# SW6208_A_A_B_C_LED__188.net
KiCad netlist of a schematic drawn in Altium Designer
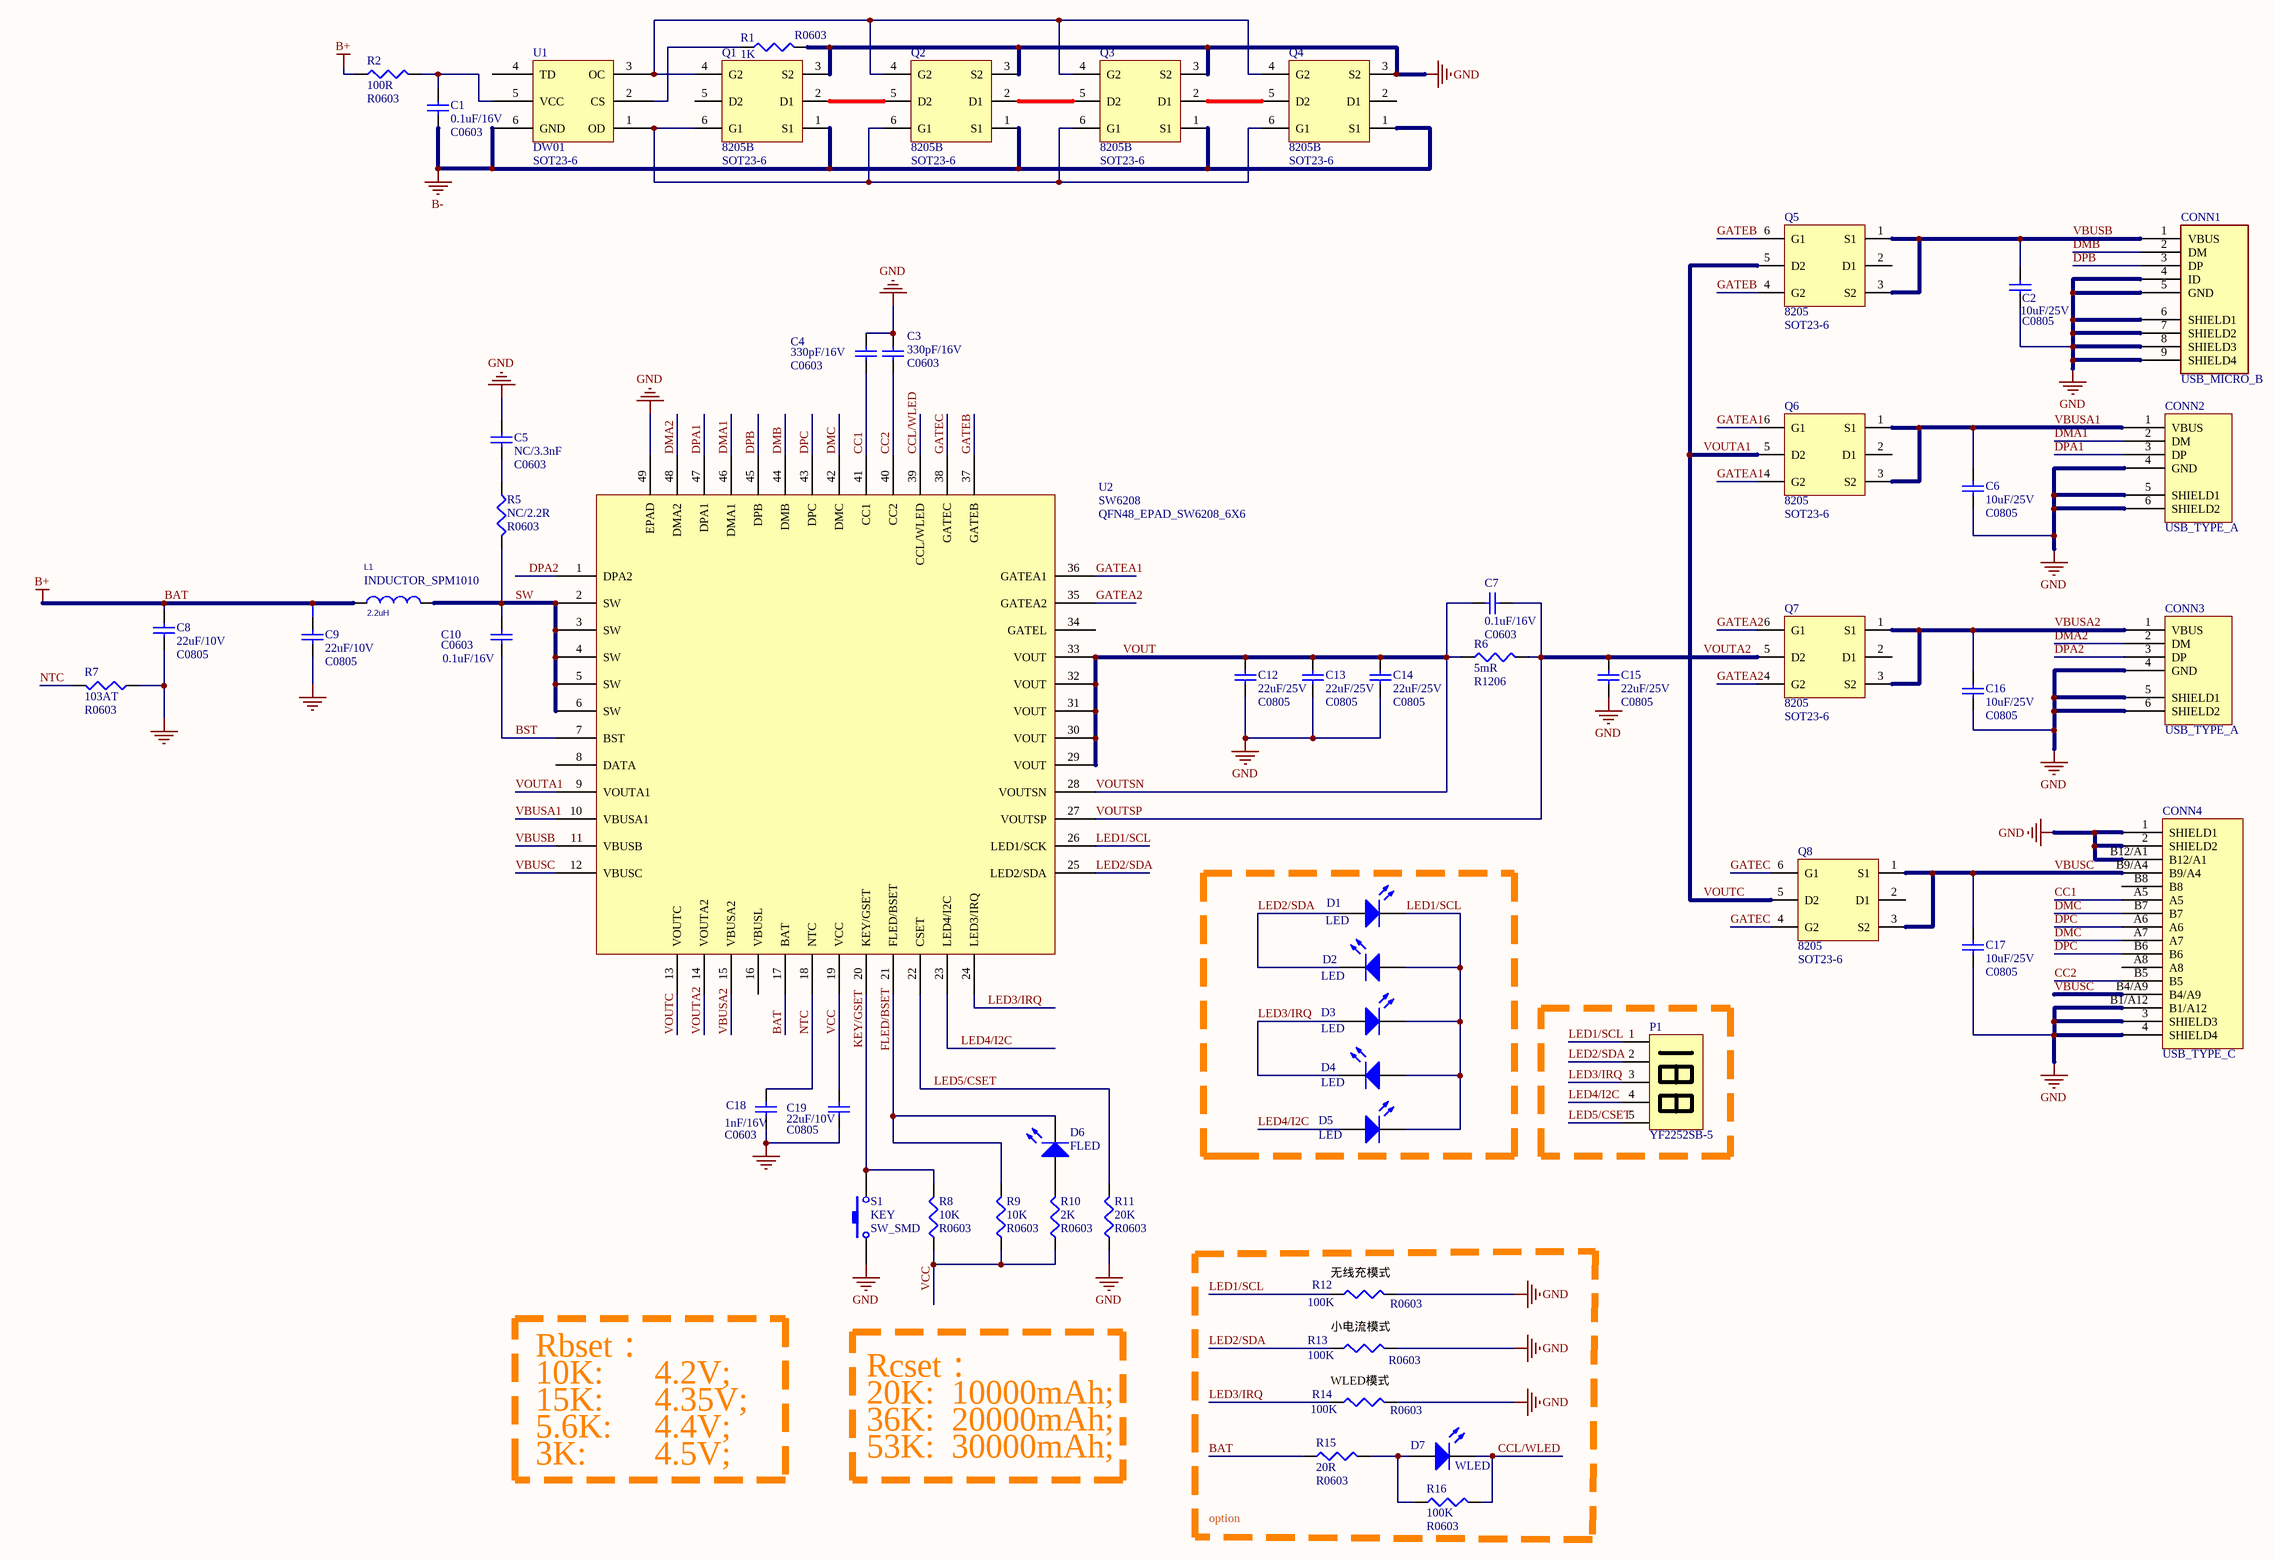
[diagram p0: SW6208+A+A+B+C+LED_普通188数码管.SchDoc]

(export (version "E")
  (design (tool "Eeschema 10.0.6"))
  (components
    (comp (ref "C1")
      (value "0.1uF/16V")
      (footprint "C0603")
      (description "Capacitor")
      (fields (field (name "PUBLISHER") "Altium Limited"))
      (libsource (lib "参考设计器件原理图更新") (part "CAP0603"))
    )
    (comp (ref "C2")
      (value "10uF/25V")
      (footprint "C0805")
      (description "Capacitor")
      (fields (field (name "PUBLISHER") "Altium Limited"))
      (libsource (lib "参考设计器件原理图更新") (part "CAP0805"))
    )
    (comp (ref "C3")
      (value "330pF/16V")
      (footprint "C0603")
      (description "Capacitor")
      (fields (field (name "PUBLISHER") "Altium Limited"))
      (libsource (lib "参考设计器件原理图更新") (part "CAP0603"))
    )
    (comp (ref "C4")
      (value "330pF/16V")
      (footprint "C0603")
      (description "Capacitor")
      (fields (field (name "PUBLISHER") "Altium Limited"))
      (libsource (lib "参考设计器件原理图更新") (part "CAP0603"))
    )
    (comp (ref "C5")
      (value "NC/3.3nF")
      (footprint "C0603")
      (description "Capacitor")
      (fields (field (name "PUBLISHER") "Altium Limited"))
      (libsource (lib "参考设计器件原理图更新") (part "CAP0603"))
    )
    (comp (ref "C6")
      (value "10uF/25V")
      (footprint "C0805")
      (description "Capacitor")
      (fields (field (name "PUBLISHER") "Altium Limited"))
      (libsource (lib "参考设计器件原理图更新") (part "CAP0805"))
    )
    (comp (ref "C7")
      (value "0.1uF/16V")
      (footprint "C0603")
      (description "Capacitor")
      (fields (field (name "PUBLISHER") "Altium Limited"))
      (libsource (lib "参考设计器件原理图更新") (part "CAP0603"))
    )
    (comp (ref "C8")
      (value "22uF/10V")
      (footprint "C0805")
      (description "Capacitor")
      (fields (field (name "PUBLISHER") "Altium Limited"))
      (libsource (lib "参考设计器件原理图更新") (part "CAP0805"))
    )
    (comp (ref "C9")
      (value "22uF/10V")
      (footprint "C0805")
      (description "Capacitor")
      (fields (field (name "PUBLISHER") "Altium Limited"))
      (libsource (lib "参考设计器件原理图更新") (part "CAP0805"))
    )
    (comp (ref "C10")
      (value "0.1uF/16V")
      (footprint "C0603")
      (description "Capacitor")
      (fields (field (name "PUBLISHER") "Altium Limited"))
      (libsource (lib "参考设计器件原理图更新") (part "CAP0603"))
    )
    (comp (ref "C12")
      (value "22uF/25V")
      (footprint "C0805")
      (description "Capacitor")
      (fields (field (name "PUBLISHER") "Altium Limited"))
      (libsource (lib "参考设计器件原理图更新") (part "CAP0805"))
    )
    (comp (ref "C13")
      (value "22uF/25V")
      (footprint "C0805")
      (description "Capacitor")
      (fields (field (name "PUBLISHER") "Altium Limited"))
      (libsource (lib "参考设计器件原理图更新") (part "CAP0805"))
    )
    (comp (ref "C14")
      (value "22uF/25V")
      (footprint "C0805")
      (description "Capacitor")
      (fields (field (name "PUBLISHER") "Altium Limited"))
      (libsource (lib "参考设计器件原理图更新") (part "CAP0805"))
    )
    (comp (ref "C15")
      (value "22uF/25V")
      (footprint "C0805")
      (description "Capacitor")
      (fields (field (name "PUBLISHER") "Altium Limited"))
      (libsource (lib "参考设计器件原理图更新") (part "CAP0805"))
    )
    (comp (ref "C16")
      (value "10uF/25V")
      (footprint "C0805")
      (description "Capacitor")
      (fields (field (name "PUBLISHER") "Altium Limited"))
      (libsource (lib "参考设计器件原理图更新") (part "CAP0805"))
    )
    (comp (ref "C17")
      (value "10uF/25V")
      (footprint "C0805")
      (description "Capacitor")
      (fields (field (name "PUBLISHER") "Altium Limited"))
      (libsource (lib "参考设计器件原理图更新") (part "CAP0805"))
    )
    (comp (ref "C18")
      (value "1nF/16V")
      (footprint "C0603")
      (description "Capacitor")
      (fields (field (name "PUBLISHER") "Altium Limited"))
      (libsource (lib "参考设计器件原理图更新") (part "CAP0603"))
    )
    (comp (ref "C19")
      (value "22uF/10V")
      (footprint "C0805")
      (description "Capacitor")
      (fields (field (name "PUBLISHER") "Altium Limited"))
      (libsource (lib "参考设计器件原理图更新") (part "CAP0805"))
    )
    (comp (ref "CONN1")
      (value "USB_MICRO_B")
      (footprint "USB_MICRO_B")
      (libsource (lib "参考设计器件原理图更新") (part "USB_MICRO_B"))
    )
    (comp (ref "CONN2")
      (value "USB_TYPE_A")
      (footprint "USB_TYPE_A")
      (libsource (lib "参考设计器件原理图更新") (part "USB_TYPE_A"))
    )
    (comp (ref "CONN3")
      (value "USB_TYPE_A")
      (footprint "USB_TYPE_A")
      (libsource (lib "参考设计器件原理图更新") (part "USB_TYPE_A"))
    )
    (comp (ref "CONN4")
      (value "USB_TYPE_C")
      (footprint "LOUISAD:USB_TYPE_C")
      (libsource (lib "参考设计器件原理图更新") (part "USB_TYPE_C"))
    )
    (comp (ref "D1")
      (value "LED")
      (footprint "LED0603")
      (fields (field (name "PUBLISHER") "Altium Limited"))
      (libsource (lib "参考设计器件原理图更新") (part "LED_0603"))
    )
    (comp (ref "D2")
      (value "LED")
      (footprint "LED0603")
      (fields (field (name "PUBLISHER") "Altium Limited"))
      (libsource (lib "参考设计器件原理图更新") (part "LED_0603"))
    )
    (comp (ref "D3")
      (value "LED")
      (footprint "LED0603")
      (fields (field (name "PUBLISHER") "Altium Limited"))
      (libsource (lib "参考设计器件原理图更新") (part "LED_0603"))
    )
    (comp (ref "D4")
      (value "LED")
      (footprint "LED0603")
      (fields (field (name "PUBLISHER") "Altium Limited"))
      (libsource (lib "参考设计器件原理图更新") (part "LED_0603"))
    )
    (comp (ref "D5")
      (value "LED")
      (footprint "LED0603")
      (fields (field (name "PUBLISHER") "Altium Limited"))
      (libsource (lib "参考设计器件原理图更新") (part "LED_0603"))
    )
    (comp (ref "D6")
      (value "FLED")
      (footprint "LED0603")
      (description "LED")
      (fields (field (name "PUBLISHER") "Altium Limited"))
      (libsource (lib "参考设计器件原理图更新") (part "LED_0603"))
    )
    (comp (ref "D7")
      (value "WLED")
      (footprint "LED_5MM")
      (fields (field (name "PUBLISHER") "Altium Limited"))
      (libsource (lib "参考设计器件原理图更新") (part "WLED"))
    )
    (comp (ref "L1")
      (value "2.2uH")
      (footprint "INDUCTOR_SPM1010")
      (description "INDUCTOR")
      (libsource (lib "参考设计器件原理图更新") (part "INDUCTOR_SPM1010"))
    )
    (comp (ref "P1")
      (value "YF2252SB-5")
      (footprint "LED_Display_5")
      (description "188_LED_Display")
      (libsource (lib "参考设计器件原理图更新") (part "LED_Display_5"))
    )
    (comp (ref "Q1")
      (value "8205B")
      (footprint "SOT23-6")
      (description "NMOS")
      (fields (field (name "FOOTPRINF") "SOT23-6"))
      (libsource (lib "参考设计器件原理图更新") (part "8205"))
    )
    (comp (ref "Q2")
      (value "8205B")
      (footprint "SOT23-6")
      (description "NMOS")
      (fields (field (name "FOOTPRINF") "SOT23-6"))
      (libsource (lib "参考设计器件原理图更新") (part "8205"))
    )
    (comp (ref "Q3")
      (value "8205B")
      (footprint "SOT23-6")
      (description "NMOS")
      (fields (field (name "FOOTPRINF") "SOT23-6"))
      (libsource (lib "参考设计器件原理图更新") (part "8205"))
    )
    (comp (ref "Q4")
      (value "8205B")
      (footprint "SOT23-6")
      (description "NMOS")
      (fields (field (name "FOOTPRINF") "SOT23-6"))
      (libsource (lib "参考设计器件原理图更新") (part "8205"))
    )
    (comp (ref "Q5")
      (value "8205")
      (footprint "SOT23-6")
      (description "NMOS")
      (fields (field (name "FOOTPRINF") "SOT23-6"))
      (libsource (lib "") (part "8205_1"))
    )
    (comp (ref "Q6")
      (value "8205")
      (footprint "SOT23-6")
      (description "NMOS")
      (fields (field (name "FOOTPRINF") "SOT23-6"))
      (libsource (lib "") (part "8205_1"))
    )
    (comp (ref "Q7")
      (value "8205")
      (footprint "SOT23-6")
      (description "NMOS")
      (fields (field (name "FOOTPRINF") "SOT23-6"))
      (libsource (lib "") (part "8205_1"))
    )
    (comp (ref "Q8")
      (value "8205")
      (footprint "SOT23-6")
      (description "NMOS")
      (fields (field (name "FOOTPRINF") "SOT23-6"))
      (libsource (lib "") (part "8205_1"))
    )
    (comp (ref "R1")
      (value "1K")
      (footprint "R0603")
      (description "Resistor")
      (fields (field (name "PUBLISHER") "Altium Limited"))
      (libsource (lib "参考设计器件原理图更新") (part "RES_0603"))
    )
    (comp (ref "R2")
      (value "100R")
      (footprint "R0603")
      (description "Resistor")
      (fields (field (name "PUBLISHER") "Altium Limited"))
      (libsource (lib "参考设计器件原理图更新") (part "RES_0603"))
    )
    (comp (ref "R5")
      (value "NC/2.2R")
      (footprint "R0603")
      (description "Resistor")
      (fields (field (name "PUBLISHER") "Altium Limited"))
      (libsource (lib "参考设计器件原理图更新") (part "RES_0603"))
    )
    (comp (ref "R6")
      (value "5mR")
      (footprint "R1206")
      (description "Resistor")
      (fields (field (name "PUBLISHER") "Altium Limited"))
      (libsource (lib "参考设计器件原理图更新") (part "RES_1206"))
    )
    (comp (ref "R7")
      (value "103AT")
      (footprint "R0603")
      (description "Resistor")
      (fields (field (name "PUBLISHER") "Altium Limited"))
      (libsource (lib "参考设计器件原理图更新") (part "RES_0603"))
    )
    (comp (ref "R8")
      (value "10K")
      (footprint "R0603")
      (description "Resistor")
      (fields (field (name "PUBLISHER") "Altium Limited"))
      (libsource (lib "参考设计器件原理图更新") (part "RES_0603"))
    )
    (comp (ref "R9")
      (value "10K")
      (footprint "R0603")
      (description "Resistor")
      (fields (field (name "PUBLISHER") "Altium Limited"))
      (libsource (lib "参考设计器件原理图更新") (part "RES_0603"))
    )
    (comp (ref "R10")
      (value "2K")
      (footprint "R0603")
      (description "Resistor")
      (fields (field (name "PUBLISHER") "Altium Limited"))
      (libsource (lib "参考设计器件原理图更新") (part "RES_0603"))
    )
    (comp (ref "R11")
      (value "20K")
      (footprint "R0603")
      (description "Resistor")
      (fields (field (name "PUBLISHER") "Altium Limited"))
      (libsource (lib "参考设计器件原理图更新") (part "RES_0603"))
    )
    (comp (ref "R12")
      (value "100K")
      (footprint "R0603")
      (description "Resistor")
      (fields (field (name "PUBLISHER") "Altium Limited"))
      (libsource (lib "参考设计器件原理图更新") (part "RES_0603"))
    )
    (comp (ref "R13")
      (value "100K")
      (footprint "R0603")
      (description "Resistor")
      (fields (field (name "PUBLISHER") "Altium Limited"))
      (libsource (lib "参考设计器件原理图更新") (part "RES_0603"))
    )
    (comp (ref "R14")
      (value "100K")
      (footprint "R0603")
      (description "Resistor")
      (fields (field (name "PUBLISHER") "Altium Limited"))
      (libsource (lib "参考设计器件原理图更新") (part "RES_0603"))
    )
    (comp (ref "R15")
      (value "20R")
      (footprint "R0603")
      (description "Resistor")
      (fields (field (name "PUBLISHER") "Altium Limited"))
      (libsource (lib "参考设计器件原理图更新") (part "RES_0603"))
    )
    (comp (ref "R16")
      (value "100K")
      (footprint "R0603")
      (description "Resistor")
      (fields (field (name "PUBLISHER") "Altium Limited"))
      (libsource (lib "参考设计器件原理图更新") (part "RES_0603"))
    )
    (comp (ref "S1")
      (value "KEY")
      (footprint "SW_SMD")
      (fields (field (name "FOOTPRINF") "SW_SMD"))
      (libsource (lib "参考设计器件原理图更新") (part "SW K"))
    )
    (comp (ref "U1")
      (value "DW01")
      (footprint "SOT23-6")
      (description "BAT_PROTECT_IC")
      (libsource (lib "参考设计器件原理图更新") (part "DW01"))
    )
    (comp (ref "U2")
      (value "SW6208")
      (footprint "QFN48_EPAD_SW6208_6X6")
      (description "IC")
      (libsource (lib "芯片型号原理图") (part "SW6208"))
    )
  )
  (nets
    (net (code "1") (name "/BST") (class "Default")
      (node (ref "C10") (pin "1") (pinfunction "1_1") (pintype "passive"))
      (node (ref "U2") (pin "7") (pinfunction "BST_7") (pintype "passive"))
    )
    (net (code "2") (name "/CC1") (class "Default")
      (node (ref "C4") (pin "1") (pinfunction "1_1") (pintype "passive"))
      (node (ref "CONN4") (pin "A5") (pinfunction "A5_A5") (pintype "passive"))
      (node (ref "U2") (pin "41") (pinfunction "CC1_41") (pintype "passive"))
    )
    (net (code "3") (name "/CC2") (class "Default")
      (node (ref "C3") (pin "1") (pinfunction "1_1") (pintype "passive"))
      (node (ref "CONN4") (pin "B5") (pinfunction "B5_B5") (pintype "passive"))
      (node (ref "U2") (pin "40") (pinfunction "CC2_40") (pintype "passive"))
    )
    (net (code "4") (name "/CCL{slash}WLED") (class "Default")
      (node (ref "D7") (pin "2") (pinfunction "K_2") (pintype "passive"))
      (node (ref "R16") (pin "2") (pinfunction "2_2") (pintype "passive"))
      (node (ref "U2") (pin "39") (pinfunction "CCL/WLED_39") (pintype "passive"))
    )
    (net (code "5") (name "/DMA1") (class "Default")
      (node (ref "CONN2") (pin "2") (pinfunction "DM_2") (pintype "passive"))
      (node (ref "U2") (pin "46") (pinfunction "DMA1_46") (pintype "passive"))
    )
    (net (code "6") (name "/DMA2") (class "Default")
      (node (ref "CONN3") (pin "2") (pinfunction "DM_2") (pintype "passive"))
      (node (ref "U2") (pin "48") (pinfunction "DMA2_48") (pintype "passive"))
    )
    (net (code "7") (name "/DMB") (class "Default")
      (node (ref "CONN1") (pin "2") (pinfunction "DM_2") (pintype "passive"))
      (node (ref "U2") (pin "44") (pinfunction "DMB_44") (pintype "passive"))
    )
    (net (code "8") (name "/DMC") (class "Default")
      (node (ref "CONN4") (pin "A7") (pinfunction "A7_A7") (pintype "passive"))
      (node (ref "CONN4") (pin "B7") (pinfunction "B7_B7") (pintype "passive"))
      (node (ref "U2") (pin "42") (pinfunction "DMC_42") (pintype "passive"))
    )
    (net (code "9") (name "/DPA1") (class "Default")
      (node (ref "CONN2") (pin "3") (pinfunction "DP_3") (pintype "passive"))
      (node (ref "U2") (pin "47") (pinfunction "DPA1_47") (pintype "passive"))
    )
    (net (code "10") (name "/DPA2") (class "Default")
      (node (ref "CONN3") (pin "3") (pinfunction "DP_3") (pintype "passive"))
      (node (ref "U2") (pin "1") (pinfunction "DPA2_1") (pintype "passive"))
    )
    (net (code "11") (name "/DPB") (class "Default")
      (node (ref "CONN1") (pin "3") (pinfunction "DP_3") (pintype "passive"))
      (node (ref "U2") (pin "45") (pinfunction "DPB_45") (pintype "passive"))
    )
    (net (code "12") (name "/DPC") (class "Default")
      (node (ref "CONN4") (pin "A6") (pinfunction "A6_A6") (pintype "passive"))
      (node (ref "CONN4") (pin "B6") (pinfunction "B6_B6") (pintype "passive"))
      (node (ref "U2") (pin "43") (pinfunction "DPC_43") (pintype "passive"))
    )
    (net (code "13") (name "/FLED{slash}BSET") (class "Default")
      (node (ref "D6") (pin "2") (pinfunction "K_2") (pintype "passive"))
      (node (ref "R9") (pin "2") (pinfunction "2_2") (pintype "passive"))
      (node (ref "U2") (pin "21") (pinfunction "FLED/BSET_21") (pintype "passive"))
    )
    (net (code "14") (name "/GATEA1") (class "Default")
      (node (ref "Q6") (pin "4") (pinfunction "G2_4") (pintype "passive"))
      (node (ref "Q6") (pin "6") (pinfunction "G1_6") (pintype "passive"))
      (node (ref "U2") (pin "36") (pinfunction "GATEA1_36") (pintype "passive"))
    )
    (net (code "15") (name "/GATEA2") (class "Default")
      (node (ref "Q7") (pin "4") (pinfunction "G2_4") (pintype "passive"))
      (node (ref "Q7") (pin "6") (pinfunction "G1_6") (pintype "passive"))
      (node (ref "U2") (pin "35") (pinfunction "GATEA2_35") (pintype "passive"))
    )
    (net (code "16") (name "/GATEB") (class "Default")
      (node (ref "Q5") (pin "4") (pinfunction "G2_4") (pintype "passive"))
      (node (ref "Q5") (pin "6") (pinfunction "G1_6") (pintype "passive"))
      (node (ref "U2") (pin "37") (pinfunction "GATEB_37") (pintype "passive"))
    )
    (net (code "17") (name "/GATEC") (class "Default")
      (node (ref "Q8") (pin "4") (pinfunction "G2_4") (pintype "passive"))
      (node (ref "Q8") (pin "6") (pinfunction "G1_6") (pintype "passive"))
      (node (ref "U2") (pin "38") (pinfunction "GATEC_38") (pintype "passive"))
    )
    (net (code "18") (name "/KEY{slash}GSET") (class "Default")
      (node (ref "R8") (pin "2") (pinfunction "2_2") (pintype "passive"))
      (node (ref "S1") (pin "2") (pinfunction "2_2") (pintype "passive"))
      (node (ref "U2") (pin "20") (pinfunction "KEY/GSET_20") (pintype "passive"))
    )
    (net (code "19") (name "/LED1{slash}SCL") (class "Default")
      (node (ref "D1") (pin "2") (pinfunction "K_2") (pintype "passive"))
      (node (ref "D2") (pin "1") (pinfunction "A_1") (pintype "passive"))
      (node (ref "D3") (pin "2") (pinfunction "K_2") (pintype "passive"))
      (node (ref "D4") (pin "1") (pinfunction "A_1") (pintype "passive"))
      (node (ref "D5") (pin "2") (pinfunction "K_2") (pintype "passive"))
      (node (ref "P1") (pin "1") (pinfunction "F_1") (pintype "passive"))
      (node (ref "R12") (pin "1") (pinfunction "1_1") (pintype "passive"))
      (node (ref "U2") (pin "26") (pinfunction "LED1/SCK_26") (pintype "passive"))
    )
    (net (code "20") (name "/LED2{slash}SDA") (class "Default")
      (node (ref "D1") (pin "1") (pinfunction "A_1") (pintype "passive"))
      (node (ref "D2") (pin "2") (pinfunction "K_2") (pintype "passive"))
      (node (ref "P1") (pin "2") (pinfunction "C_2") (pintype "passive"))
      (node (ref "R13") (pin "1") (pinfunction "1_1") (pintype "passive"))
      (node (ref "U2") (pin "25") (pinfunction "LED2/SDA_25") (pintype "passive"))
    )
    (net (code "21") (name "/LED3{slash}IRQ") (class "Default")
      (node (ref "D3") (pin "1") (pinfunction "A_1") (pintype "passive"))
      (node (ref "D4") (pin "2") (pinfunction "K_2") (pintype "passive"))
      (node (ref "P1") (pin "3") (pinfunction "D_3") (pintype "passive"))
      (node (ref "R14") (pin "1") (pinfunction "1_1") (pintype "passive"))
      (node (ref "U2") (pin "24") (pinfunction "LED3/IRQ_24") (pintype "passive"))
    )
    (net (code "22") (name "/LED4{slash}I2C") (class "Default")
      (node (ref "D5") (pin "1") (pinfunction "A_1") (pintype "passive"))
      (node (ref "P1") (pin "4") (pinfunction "E_4") (pintype "passive"))
      (node (ref "U2") (pin "23") (pinfunction "LED4/I2C_23") (pintype "passive"))
    )
    (net (code "23") (name "/LED5{slash}CSET") (class "Default")
      (node (ref "P1") (pin "5") (pinfunction "G_5") (pintype "passive"))
      (node (ref "R11") (pin "2") (pinfunction "2_2") (pintype "passive"))
      (node (ref "U2") (pin "22") (pinfunction "CSET_22") (pintype "passive"))
    )
    (net (code "24") (name "/NTC") (class "Default")
      (node (ref "C18") (pin "1") (pinfunction "1_1") (pintype "passive"))
      (node (ref "R7") (pin "2") (pinfunction "2_2") (pintype "passive"))
      (node (ref "U2") (pin "18") (pinfunction "NTC_18") (pintype "passive"))
    )
    (net (code "25") (name "/SW") (class "Default")
      (node (ref "C10") (pin "2") (pinfunction "2_2") (pintype "passive"))
      (node (ref "L1") (pin "2") (pinfunction "2_2") (pintype "passive"))
      (node (ref "R5") (pin "2") (pinfunction "2_2") (pintype "passive"))
      (node (ref "U2") (pin "2") (pinfunction "SW_2") (pintype "passive"))
      (node (ref "U2") (pin "3") (pinfunction "SW_3") (pintype "passive"))
      (node (ref "U2") (pin "4") (pinfunction "SW_4") (pintype "passive"))
      (node (ref "U2") (pin "5") (pinfunction "SW_5") (pintype "passive"))
      (node (ref "U2") (pin "6") (pinfunction "SW_6") (pintype "passive"))
    )
    (net (code "26") (name "/VBUSA1") (class "Default")
      (node (ref "C6") (pin "2") (pinfunction "2_2") (pintype "passive"))
      (node (ref "CONN2") (pin "1") (pinfunction "VBUS_1") (pintype "passive"))
      (node (ref "Q6") (pin "1") (pinfunction "S1_1") (pintype "passive"))
      (node (ref "Q6") (pin "3") (pinfunction "S2_3") (pintype "passive"))
      (node (ref "U2") (pin "10") (pinfunction "VBUSA1_10") (pintype "passive"))
    )
    (net (code "27") (name "/VBUSA2") (class "Default")
      (node (ref "C16") (pin "2") (pinfunction "2_2") (pintype "passive"))
      (node (ref "CONN3") (pin "1") (pinfunction "VBUS_1") (pintype "passive"))
      (node (ref "Q7") (pin "1") (pinfunction "S1_1") (pintype "passive"))
      (node (ref "Q7") (pin "3") (pinfunction "S2_3") (pintype "passive"))
      (node (ref "U2") (pin "15") (pinfunction "VBUSA2_15") (pintype "passive"))
    )
    (net (code "28") (name "/VBUSB") (class "Default")
      (node (ref "C2") (pin "2") (pinfunction "2_2") (pintype "passive"))
      (node (ref "CONN1") (pin "1") (pinfunction "VBUS_1") (pintype "passive"))
      (node (ref "Q5") (pin "1") (pinfunction "S1_1") (pintype "passive"))
      (node (ref "Q5") (pin "3") (pinfunction "S2_3") (pintype "passive"))
      (node (ref "U2") (pin "11") (pinfunction "VBUSB_11") (pintype "passive"))
    )
    (net (code "29") (name "/VBUSC") (class "Default")
      (node (ref "C17") (pin "2") (pinfunction "2_2") (pintype "passive"))
      (node (ref "CONN4") (pin "B4/A9") (pinfunction "B4/A9_B4/A9") (pintype "passive"))
      (node (ref "CONN4") (pin "B9/A4") (pinfunction "B9/A4_B9/A4") (pintype "passive"))
      (node (ref "Q8") (pin "1") (pinfunction "S1_1") (pintype "passive"))
      (node (ref "Q8") (pin "3") (pinfunction "S2_3") (pintype "passive"))
      (node (ref "U2") (pin "12") (pinfunction "VBUSC_12") (pintype "passive"))
    )
    (net (code "30") (name "/VCC") (class "Default")
      (node (ref "C19") (pin "1") (pinfunction "1_1") (pintype "passive"))
      (node (ref "R10") (pin "1") (pinfunction "1_1") (pintype "passive"))
      (node (ref "R8") (pin "1") (pinfunction "1_1") (pintype "passive"))
      (node (ref "R9") (pin "1") (pinfunction "1_1") (pintype "passive"))
      (node (ref "U2") (pin "19") (pinfunction "VCC_19") (pintype "passive"))
    )
    (net (code "31") (name "/VOUT") (class "Default")
      (node (ref "C12") (pin "2") (pinfunction "2_2") (pintype "passive"))
      (node (ref "C13") (pin "2") (pinfunction "2_2") (pintype "passive"))
      (node (ref "C14") (pin "2") (pinfunction "2_2") (pintype "passive"))
      (node (ref "C7") (pin "1") (pinfunction "1_1") (pintype "passive"))
      (node (ref "R6") (pin "1") (pinfunction "1_1") (pintype "passive"))
      (node (ref "U2") (pin "28") (pinfunction "VOUTSN_28") (pintype "passive"))
      (node (ref "U2") (pin "29") (pinfunction "VOUT_29") (pintype "passive"))
      (node (ref "U2") (pin "30") (pinfunction "VOUT_30") (pintype "passive"))
      (node (ref "U2") (pin "31") (pinfunction "VOUT_31") (pintype "passive"))
      (node (ref "U2") (pin "32") (pinfunction "VOUT_32") (pintype "passive"))
      (node (ref "U2") (pin "33") (pinfunction "VOUT_33") (pintype "passive"))
    )
    (net (code "32") (name "/VOUTA1") (class "Default")
      (node (ref "Q5") (pin "5") (pinfunction "D2_5") (pintype "passive"))
      (node (ref "Q6") (pin "5") (pinfunction "D2_5") (pintype "passive"))
      (node (ref "Q8") (pin "5") (pinfunction "D2_5") (pintype "passive"))
      (node (ref "U2") (pin "13") (pinfunction "VOUTC_13") (pintype "passive"))
      (node (ref "U2") (pin "9") (pinfunction "VOUTA1_9") (pintype "passive"))
    )
    (net (code "33") (name "/VOUTA2") (class "Default")
      (node (ref "C15") (pin "2") (pinfunction "2_2") (pintype "passive"))
      (node (ref "C7") (pin "2") (pinfunction "2_2") (pintype "passive"))
      (node (ref "Q7") (pin "5") (pinfunction "D2_5") (pintype "passive"))
      (node (ref "R6") (pin "2") (pinfunction "2_2") (pintype "passive"))
      (node (ref "U2") (pin "14") (pinfunction "VOUTA2_14") (pintype "passive"))
      (node (ref "U2") (pin "27") (pinfunction "VOUTSP_27") (pintype "passive"))
    )
    (net (code "34") (name "B+") (class "Default")
      (node (ref "C8") (pin "2") (pinfunction "2_2") (pintype "passive"))
      (node (ref "C9") (pin "2") (pinfunction "2_2") (pintype "passive"))
      (node (ref "L1") (pin "1") (pinfunction "1_1") (pintype "passive"))
      (node (ref "R15") (pin "1") (pinfunction "1_1") (pintype "passive"))
      (node (ref "R2") (pin "1") (pinfunction "1_1") (pintype "passive"))
      (node (ref "U2") (pin "17") (pinfunction "BAT_17") (pintype "passive"))
    )
    (net (code "35") (name "B-") (class "Default")
      (node (ref "C1") (pin "1") (pinfunction "1_1") (pintype "passive"))
      (node (ref "Q1") (pin "1") (pinfunction "S1_1") (pintype "passive"))
      (node (ref "Q2") (pin "1") (pinfunction "S1_1") (pintype "passive"))
      (node (ref "Q3") (pin "1") (pinfunction "S1_1") (pintype "passive"))
      (node (ref "Q4") (pin "1") (pinfunction "S1_1") (pintype "passive"))
      (node (ref "U1") (pin "6") (pinfunction "GND_6") (pintype "passive"))
    )
    (net (code "36") (name "GND") (class "Default")
      (node (ref "C12") (pin "1") (pinfunction "1_1") (pintype "passive"))
      (node (ref "C13") (pin "1") (pinfunction "1_1") (pintype "passive"))
      (node (ref "C14") (pin "1") (pinfunction "1_1") (pintype "passive"))
      (node (ref "C15") (pin "1") (pinfunction "1_1") (pintype "passive"))
      (node (ref "C16") (pin "1") (pinfunction "1_1") (pintype "passive"))
      (node (ref "C17") (pin "1") (pinfunction "1_1") (pintype "passive"))
      (node (ref "C18") (pin "2") (pinfunction "2_2") (pintype "passive"))
      (node (ref "C19") (pin "2") (pinfunction "2_2") (pintype "passive"))
      (node (ref "C2") (pin "1") (pinfunction "1_1") (pintype "passive"))
      (node (ref "C3") (pin "2") (pinfunction "2_2") (pintype "passive"))
      (node (ref "C4") (pin "2") (pinfunction "2_2") (pintype "passive"))
      (node (ref "C5") (pin "2") (pinfunction "2_2") (pintype "passive"))
      (node (ref "C6") (pin "1") (pinfunction "1_1") (pintype "passive"))
      (node (ref "C8") (pin "1") (pinfunction "1_1") (pintype "passive"))
      (node (ref "C9") (pin "1") (pinfunction "1_1") (pintype "passive"))
      (node (ref "CONN1") (pin "4") (pinfunction "ID_4") (pintype "passive"))
      (node (ref "CONN1") (pin "5") (pinfunction "GND_5") (pintype "passive"))
      (node (ref "CONN1") (pin "6") (pinfunction "SHIELD1_6") (pintype "passive"))
      (node (ref "CONN1") (pin "7") (pinfunction "SHIELD2_7") (pintype "passive"))
      (node (ref "CONN1") (pin "8") (pinfunction "SHIELD3_8") (pintype "passive"))
      (node (ref "CONN1") (pin "9") (pinfunction "SHIELD4_9") (pintype "passive"))
      (node (ref "CONN2") (pin "4") (pinfunction "GND_4") (pintype "passive"))
      (node (ref "CONN2") (pin "5") (pinfunction "SHIELD1_5") (pintype "passive"))
      (node (ref "CONN2") (pin "6") (pinfunction "SHIELD2_6") (pintype "passive"))
      (node (ref "CONN3") (pin "4") (pinfunction "GND_4") (pintype "passive"))
      (node (ref "CONN3") (pin "5") (pinfunction "SHIELD1_5") (pintype "passive"))
      (node (ref "CONN3") (pin "6") (pinfunction "SHIELD2_6") (pintype "passive"))
      (node (ref "CONN4") (pin "1") (pinfunction "SHIELD1_1") (pintype "passive"))
      (node (ref "CONN4") (pin "2") (pinfunction "SHIELD2_2") (pintype "passive"))
      (node (ref "CONN4") (pin "3") (pinfunction "SHIELD3_3") (pintype "passive"))
      (node (ref "CONN4") (pin "4") (pinfunction "SHIELD4_4") (pintype "passive"))
      (node (ref "CONN4") (pin "B1/A12") (pinfunction "B1/A12_B1/A12") (pintype "passive"))
      (node (ref "CONN4") (pin "B12/A1") (pinfunction "B12/A1_B12/A1") (pintype "passive"))
      (node (ref "Q1") (pin "3") (pinfunction "S2_3") (pintype "passive"))
      (node (ref "Q2") (pin "3") (pinfunction "S2_3") (pintype "passive"))
      (node (ref "Q3") (pin "3") (pinfunction "S2_3") (pintype "passive"))
      (node (ref "Q4") (pin "3") (pinfunction "S2_3") (pintype "passive"))
      (node (ref "R1") (pin "2") (pinfunction "2_2") (pintype "passive"))
      (node (ref "R11") (pin "1") (pinfunction "1_1") (pintype "passive"))
      (node (ref "R12") (pin "2") (pinfunction "2_2") (pintype "passive"))
      (node (ref "R13") (pin "2") (pinfunction "2_2") (pintype "passive"))
      (node (ref "R14") (pin "2") (pinfunction "2_2") (pintype "passive"))
      (node (ref "R7") (pin "1") (pinfunction "1_1") (pintype "passive"))
      (node (ref "S1") (pin "1") (pinfunction "1_1") (pintype "passive"))
      (node (ref "U2") (pin "49") (pinfunction "EPAD_49") (pintype "passive"))
    )
    (net (code "37") (name "Net-(C5-Pad1)") (class "Default")
      (node (ref "C5") (pin "1") (pinfunction "1_1") (pintype "passive"))
      (node (ref "R5") (pin "1") (pinfunction "1_1") (pintype "passive"))
    )
    (net (code "38") (name "Net-(D6-A)") (class "Default")
      (node (ref "D6") (pin "1") (pinfunction "A_1") (pintype "passive"))
      (node (ref "R10") (pin "2") (pinfunction "2_2") (pintype "passive"))
    )
    (net (code "39") (name "Net-(D7-A)") (class "Default")
      (node (ref "D7") (pin "1") (pinfunction "A_1") (pintype "passive"))
      (node (ref "R15") (pin "2") (pinfunction "2_2") (pintype "passive"))
      (node (ref "R16") (pin "1") (pinfunction "1_1") (pintype "passive"))
    )
    (net (code "40") (name "Net-(Q1-D1)") (class "Default")
      (node (ref "Q1") (pin "2") (pinfunction "D1_2") (pintype "passive"))
      (node (ref "Q2") (pin "5") (pinfunction "D2_5") (pintype "passive"))
    )
    (net (code "41") (name "Net-(Q1-G1)") (class "Default")
      (node (ref "Q1") (pin "6") (pinfunction "G1_6") (pintype "passive"))
      (node (ref "Q2") (pin "6") (pinfunction "G1_6") (pintype "passive"))
      (node (ref "Q3") (pin "6") (pinfunction "G1_6") (pintype "passive"))
      (node (ref "Q4") (pin "6") (pinfunction "G1_6") (pintype "passive"))
      (node (ref "U1") (pin "1") (pinfunction "OD_1") (pintype "passive"))
    )
    (net (code "42") (name "Net-(Q1-G2)") (class "Default")
      (node (ref "Q1") (pin "4") (pinfunction "G2_4") (pintype "passive"))
      (node (ref "Q2") (pin "4") (pinfunction "G2_4") (pintype "passive"))
      (node (ref "Q3") (pin "4") (pinfunction "G2_4") (pintype "passive"))
      (node (ref "Q4") (pin "4") (pinfunction "G2_4") (pintype "passive"))
      (node (ref "U1") (pin "3") (pinfunction "OC_3") (pintype "passive"))
    )
    (net (code "43") (name "Net-(Q2-D1)") (class "Default")
      (node (ref "Q2") (pin "2") (pinfunction "D1_2") (pintype "passive"))
      (node (ref "Q3") (pin "5") (pinfunction "D2_5") (pintype "passive"))
    )
    (net (code "44") (name "Net-(Q3-D1)") (class "Default")
      (node (ref "Q3") (pin "2") (pinfunction "D1_2") (pintype "passive"))
      (node (ref "Q4") (pin "5") (pinfunction "D2_5") (pintype "passive"))
    )
    (net (code "45") (name "Net-(U1-CS)") (class "Default")
      (node (ref "R1") (pin "1") (pinfunction "1_1") (pintype "passive"))
      (node (ref "U1") (pin "2") (pinfunction "CS_2") (pintype "passive"))
    )
    (net (code "46") (name "Net-(U1-VCC)") (class "Default")
      (node (ref "C1") (pin "2") (pinfunction "2_2") (pintype "passive"))
      (node (ref "R2") (pin "2") (pinfunction "2_2") (pintype "passive"))
      (node (ref "U1") (pin "5") (pinfunction "VCC_5") (pintype "passive"))
    )
    (net (code "47") (name "unconnected-(CONN4-PadA8)") (class "Default")
      (node (ref "CONN4") (pin "A8") (pinfunction "A8_A8") (pintype "passive"))
    )
    (net (code "48") (name "unconnected-(CONN4-PadB8)") (class "Default")
      (node (ref "CONN4") (pin "B8") (pinfunction "B8_B8") (pintype "passive"))
    )
    (net (code "49") (name "unconnected-(Q1-D2-Pad5)") (class "Default")
      (node (ref "Q1") (pin "5") (pinfunction "D2_5") (pintype "passive"))
    )
    (net (code "50") (name "unconnected-(Q4-D1-Pad2)") (class "Default")
      (node (ref "Q4") (pin "2") (pinfunction "D1_2") (pintype "passive"))
    )
    (net (code "51") (name "unconnected-(Q5-D1-Pad2)") (class "Default")
      (node (ref "Q5") (pin "2") (pinfunction "D1_2") (pintype "passive"))
    )
    (net (code "52") (name "unconnected-(Q6-D1-Pad2)") (class "Default")
      (node (ref "Q6") (pin "2") (pinfunction "D1_2") (pintype "passive"))
    )
    (net (code "53") (name "unconnected-(Q7-D1-Pad2)") (class "Default")
      (node (ref "Q7") (pin "2") (pinfunction "D1_2") (pintype "passive"))
    )
    (net (code "54") (name "unconnected-(Q8-D1-Pad2)") (class "Default")
      (node (ref "Q8") (pin "2") (pinfunction "D1_2") (pintype "passive"))
    )
    (net (code "55") (name "unconnected-(U1-TD-Pad4)") (class "Default")
      (node (ref "U1") (pin "4") (pinfunction "TD_4") (pintype "passive"))
    )
    (net (code "56") (name "unconnected-(U2-DATA-Pad8)") (class "Default")
      (node (ref "U2") (pin "8") (pinfunction "DATA_8") (pintype "passive"))
    )
    (net (code "57") (name "unconnected-(U2-GATEL-Pad34)") (class "Default")
      (node (ref "U2") (pin "34") (pinfunction "GATEL_34") (pintype "passive"))
    )
    (net (code "58") (name "unconnected-(U2-VBUSL-Pad16)") (class "Default")
      (node (ref "U2") (pin "16") (pinfunction "VBUSL_16") (pintype "passive"))
    )
  )
)
